# PCB-ENCODER.net
KiCad netlist of a schematic drawn in EAGLE
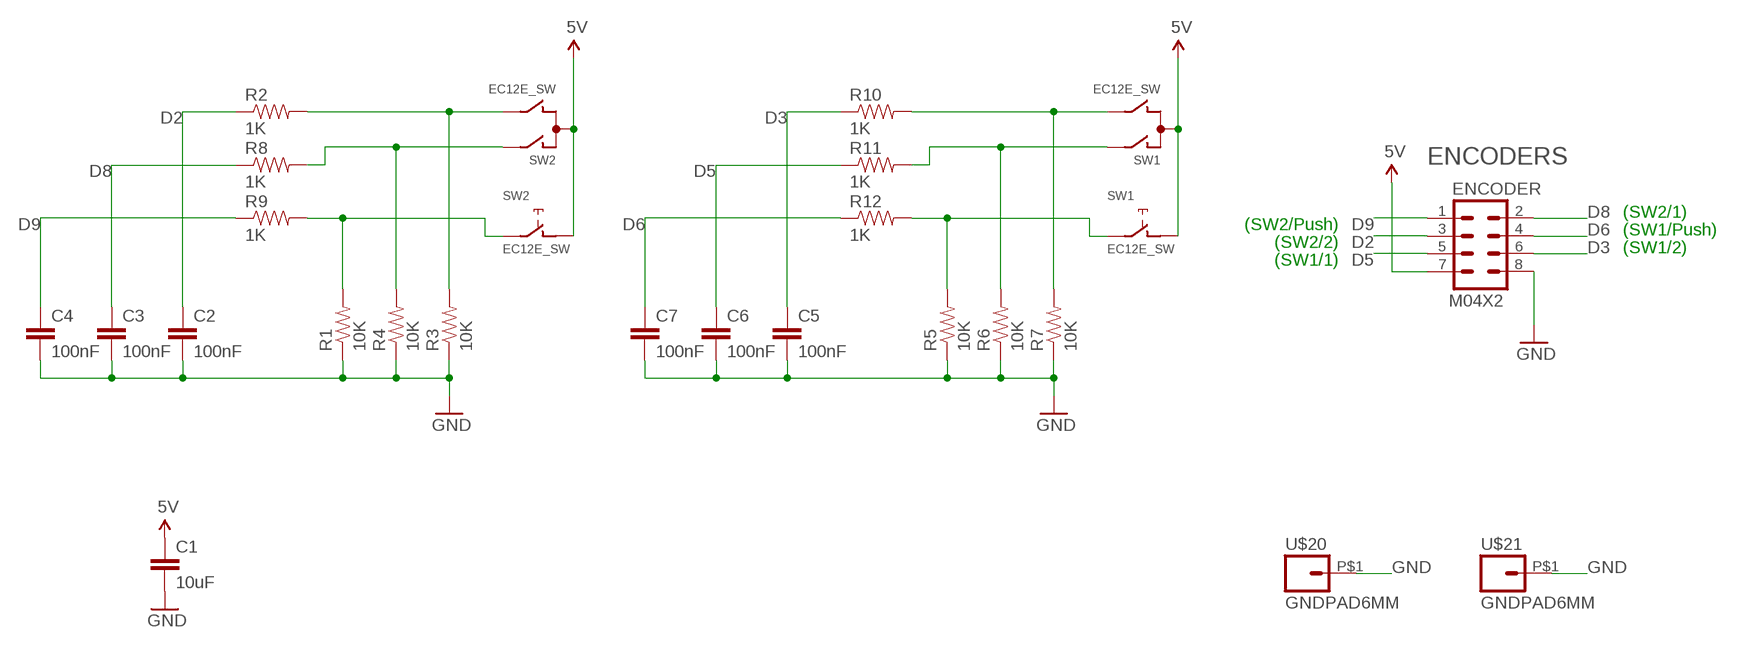
[diagram p0: schematic, sheet 1]

(export (version "E")
  (design (tool "Eeschema 10.0.6"))
  (components
    (comp (ref "C1")
      (value "10uF")
      (footprint "eagle-import:0603-CAP")
      (libsource (lib "eagle-import") (part "CAP0603-CAP"))
    )
    (comp (ref "C2")
      (value "100nF")
      (footprint "eagle-import:0603-CAP")
      (libsource (lib "eagle-import") (part "CAP0603-CAP"))
    )
    (comp (ref "C3")
      (value "100nF")
      (footprint "eagle-import:0603-CAP")
      (libsource (lib "eagle-import") (part "CAP0603-CAP"))
    )
    (comp (ref "C4")
      (value "100nF")
      (footprint "eagle-import:0603-CAP")
      (libsource (lib "eagle-import") (part "CAP0603-CAP"))
    )
    (comp (ref "C5")
      (value "100nF")
      (footprint "eagle-import:0603-CAP")
      (libsource (lib "eagle-import") (part "CAP0603-CAP"))
    )
    (comp (ref "C6")
      (value "100nF")
      (footprint "eagle-import:0603-CAP")
      (libsource (lib "eagle-import") (part "CAP0603-CAP"))
    )
    (comp (ref "C7")
      (value "100nF")
      (footprint "eagle-import:0603-CAP")
      (libsource (lib "eagle-import") (part "CAP0603-CAP"))
    )
    (comp (ref "ENCODER")
      (value "M04X2")
      (footprint "eagle-import:2X4")
      (libsource (lib "eagle-import") (part "M04X2"))
    )
    (comp (ref "R1")
      (value "10K")
      (footprint "eagle-import:0603-RES")
      (libsource (lib "eagle-import") (part "RESISTOR0603-RES"))
    )
    (comp (ref "R2")
      (value "1K")
      (footprint "eagle-import:0603-RES")
      (libsource (lib "eagle-import") (part "RESISTOR0603-RES"))
    )
    (comp (ref "R3")
      (value "10K")
      (footprint "eagle-import:0603-RES")
      (libsource (lib "eagle-import") (part "RESISTOR0603-RES"))
    )
    (comp (ref "R4")
      (value "10K")
      (footprint "eagle-import:0603-RES")
      (libsource (lib "eagle-import") (part "RESISTOR0603-RES"))
    )
    (comp (ref "R5")
      (value "10K")
      (footprint "eagle-import:0603-RES")
      (libsource (lib "eagle-import") (part "RESISTOR0603-RES"))
    )
    (comp (ref "R6")
      (value "10K")
      (footprint "eagle-import:0603-RES")
      (libsource (lib "eagle-import") (part "RESISTOR0603-RES"))
    )
    (comp (ref "R7")
      (value "10K")
      (footprint "eagle-import:0603-RES")
      (libsource (lib "eagle-import") (part "RESISTOR0603-RES"))
    )
    (comp (ref "R8")
      (value "1K")
      (footprint "eagle-import:0603-RES")
      (libsource (lib "eagle-import") (part "RESISTOR0603-RES"))
    )
    (comp (ref "R9")
      (value "1K")
      (footprint "eagle-import:0603-RES")
      (libsource (lib "eagle-import") (part "RESISTOR0603-RES"))
    )
    (comp (ref "R10")
      (value "1K")
      (footprint "eagle-import:0603-RES")
      (libsource (lib "eagle-import") (part "RESISTOR0603-RES"))
    )
    (comp (ref "R11")
      (value "1K")
      (footprint "eagle-import:0603-RES")
      (libsource (lib "eagle-import") (part "RESISTOR0603-RES"))
    )
    (comp (ref "R12")
      (value "1K")
      (footprint "eagle-import:0603-RES")
      (libsource (lib "eagle-import") (part "RESISTOR0603-RES"))
    )
    (comp (ref "SW1")
      (value "EC12E_SW")
      (footprint "eagle-import:ALPS_EC12E_SW")
      (fields (field (name "MPN") "EC12E2424407"))
      (libsource (lib "eagle-import") (part "EC12E_SW"))
    )
    (comp (ref "SW2")
      (value "EC12E_SW")
      (footprint "eagle-import:ALPS_EC12E_SW")
      (fields (field (name "MPN") "EC12E2424407"))
      (libsource (lib "eagle-import") (part "EC12E_SW"))
    )
    (comp (ref "U$20")
      (value "GNDPAD6MM")
      (footprint "eagle-import:3.2MMPAD6MM")
      (libsource (lib "eagle-import") (part "GNDPAD6MM"))
    )
    (comp (ref "U$21")
      (value "GNDPAD6MM")
      (footprint "eagle-import:3.2MMPAD6MM")
      (libsource (lib "eagle-import") (part "GNDPAD6MM"))
    )
  )
  (nets
    (net (code "1") (name "/D2") (class "Default")
      (node (ref "C2") (pin "1") (pinfunction "1_1") (pintype "passive"))
      (node (ref "ENCODER") (pin "3") (pinfunction "3_3") (pintype "passive"))
      (node (ref "R2") (pin "1") (pinfunction "1_1") (pintype "passive"))
    )
    (net (code "2") (name "/D3") (class "Default")
      (node (ref "C5") (pin "1") (pinfunction "1_1") (pintype "passive"))
      (node (ref "ENCODER") (pin "6") (pinfunction "6_6") (pintype "passive"))
      (node (ref "R10") (pin "1") (pinfunction "1_1") (pintype "passive"))
    )
    (net (code "3") (name "/D5") (class "Default")
      (node (ref "C6") (pin "1") (pinfunction "1_1") (pintype "passive"))
      (node (ref "ENCODER") (pin "5") (pinfunction "5_5") (pintype "passive"))
      (node (ref "R11") (pin "1") (pinfunction "1_1") (pintype "passive"))
    )
    (net (code "4") (name "/D6") (class "Default")
      (node (ref "C7") (pin "1") (pinfunction "1_1") (pintype "passive"))
      (node (ref "ENCODER") (pin "4") (pinfunction "4_4") (pintype "passive"))
      (node (ref "R12") (pin "1") (pinfunction "1_1") (pintype "passive"))
    )
    (net (code "5") (name "/D8") (class "Default")
      (node (ref "C3") (pin "1") (pinfunction "1_1") (pintype "passive"))
      (node (ref "ENCODER") (pin "2") (pinfunction "2_2") (pintype "passive"))
      (node (ref "R8") (pin "1") (pinfunction "1_1") (pintype "passive"))
    )
    (net (code "6") (name "/D9") (class "Default")
      (node (ref "C4") (pin "1") (pinfunction "1_1") (pintype "passive"))
      (node (ref "ENCODER") (pin "1") (pinfunction "1_1") (pintype "passive"))
      (node (ref "R9") (pin "1") (pinfunction "1_1") (pintype "passive"))
    )
    (net (code "7") (name "5V") (class "Default")
      (node (ref "C1") (pin "1") (pinfunction "1_1") (pintype "passive"))
      (node (ref "ENCODER") (pin "7") (pinfunction "7_7") (pintype "passive"))
      (node (ref "SW1") (pin "C") (pinfunction "C_C") (pintype "passive"))
      (node (ref "SW1") (pin "D") (pinfunction "1_D") (pintype "passive"))
      (node (ref "SW2") (pin "C") (pinfunction "C_C") (pintype "passive"))
      (node (ref "SW2") (pin "D") (pinfunction "1_D") (pintype "passive"))
    )
    (net (code "8") (name "GND") (class "Default")
      (node (ref "C1") (pin "2") (pinfunction "2_2") (pintype "passive"))
      (node (ref "C2") (pin "2") (pinfunction "2_2") (pintype "passive"))
      (node (ref "C3") (pin "2") (pinfunction "2_2") (pintype "passive"))
      (node (ref "C4") (pin "2") (pinfunction "2_2") (pintype "passive"))
      (node (ref "C5") (pin "2") (pinfunction "2_2") (pintype "passive"))
      (node (ref "C6") (pin "2") (pinfunction "2_2") (pintype "passive"))
      (node (ref "C7") (pin "2") (pinfunction "2_2") (pintype "passive"))
      (node (ref "ENCODER") (pin "8") (pinfunction "8_8") (pintype "passive"))
      (node (ref "R1") (pin "1") (pinfunction "1_1") (pintype "passive"))
      (node (ref "R3") (pin "1") (pinfunction "1_1") (pintype "passive"))
      (node (ref "R4") (pin "1") (pinfunction "1_1") (pintype "passive"))
      (node (ref "R5") (pin "1") (pinfunction "1_1") (pintype "passive"))
      (node (ref "R6") (pin "1") (pinfunction "1_1") (pintype "passive"))
      (node (ref "R7") (pin "1") (pinfunction "1_1") (pintype "passive"))
      (node (ref "U$20") (pin "P$1") (pinfunction "1_P$1") (pintype "passive"))
      (node (ref "U$21") (pin "P$1") (pinfunction "1_P$1") (pintype "passive"))
    )
    (net (code "9") (name "Net-(R2-Pad2)") (class "Default")
      (node (ref "R2") (pin "2") (pinfunction "2_2") (pintype "passive"))
      (node (ref "R3") (pin "2") (pinfunction "2_2") (pintype "passive"))
      (node (ref "SW2") (pin "B") (pinfunction "B_B") (pintype "passive"))
    )
    (net (code "10") (name "Net-(R4-Pad2)") (class "Default")
      (node (ref "R4") (pin "2") (pinfunction "2_2") (pintype "passive"))
      (node (ref "R8") (pin "2") (pinfunction "2_2") (pintype "passive"))
      (node (ref "SW2") (pin "A") (pinfunction "A_A") (pintype "passive"))
    )
    (net (code "11") (name "Net-(R10-Pad2)") (class "Default")
      (node (ref "R10") (pin "2") (pinfunction "2_2") (pintype "passive"))
      (node (ref "R7") (pin "2") (pinfunction "2_2") (pintype "passive"))
      (node (ref "SW1") (pin "B") (pinfunction "B_B") (pintype "passive"))
    )
    (net (code "12") (name "Net-(R11-Pad2)") (class "Default")
      (node (ref "R11") (pin "2") (pinfunction "2_2") (pintype "passive"))
      (node (ref "R6") (pin "2") (pinfunction "2_2") (pintype "passive"))
      (node (ref "SW1") (pin "A") (pinfunction "A_A") (pintype "passive"))
    )
    (net (code "13") (name "Net-(SW1B-2)") (class "Default")
      (node (ref "R12") (pin "2") (pinfunction "2_2") (pintype "passive"))
      (node (ref "R5") (pin "2") (pinfunction "2_2") (pintype "passive"))
      (node (ref "SW1") (pin "E") (pinfunction "2_E") (pintype "passive"))
    )
    (net (code "14") (name "Net-(SW2B-2)") (class "Default")
      (node (ref "R1") (pin "2") (pinfunction "2_2") (pintype "passive"))
      (node (ref "R9") (pin "2") (pinfunction "2_2") (pintype "passive"))
      (node (ref "SW2") (pin "E") (pinfunction "2_E") (pintype "passive"))
    )
  )
)
